# yard-ice-ethernet.net
KiCad netlist of a schematic drawn in Altium Designer
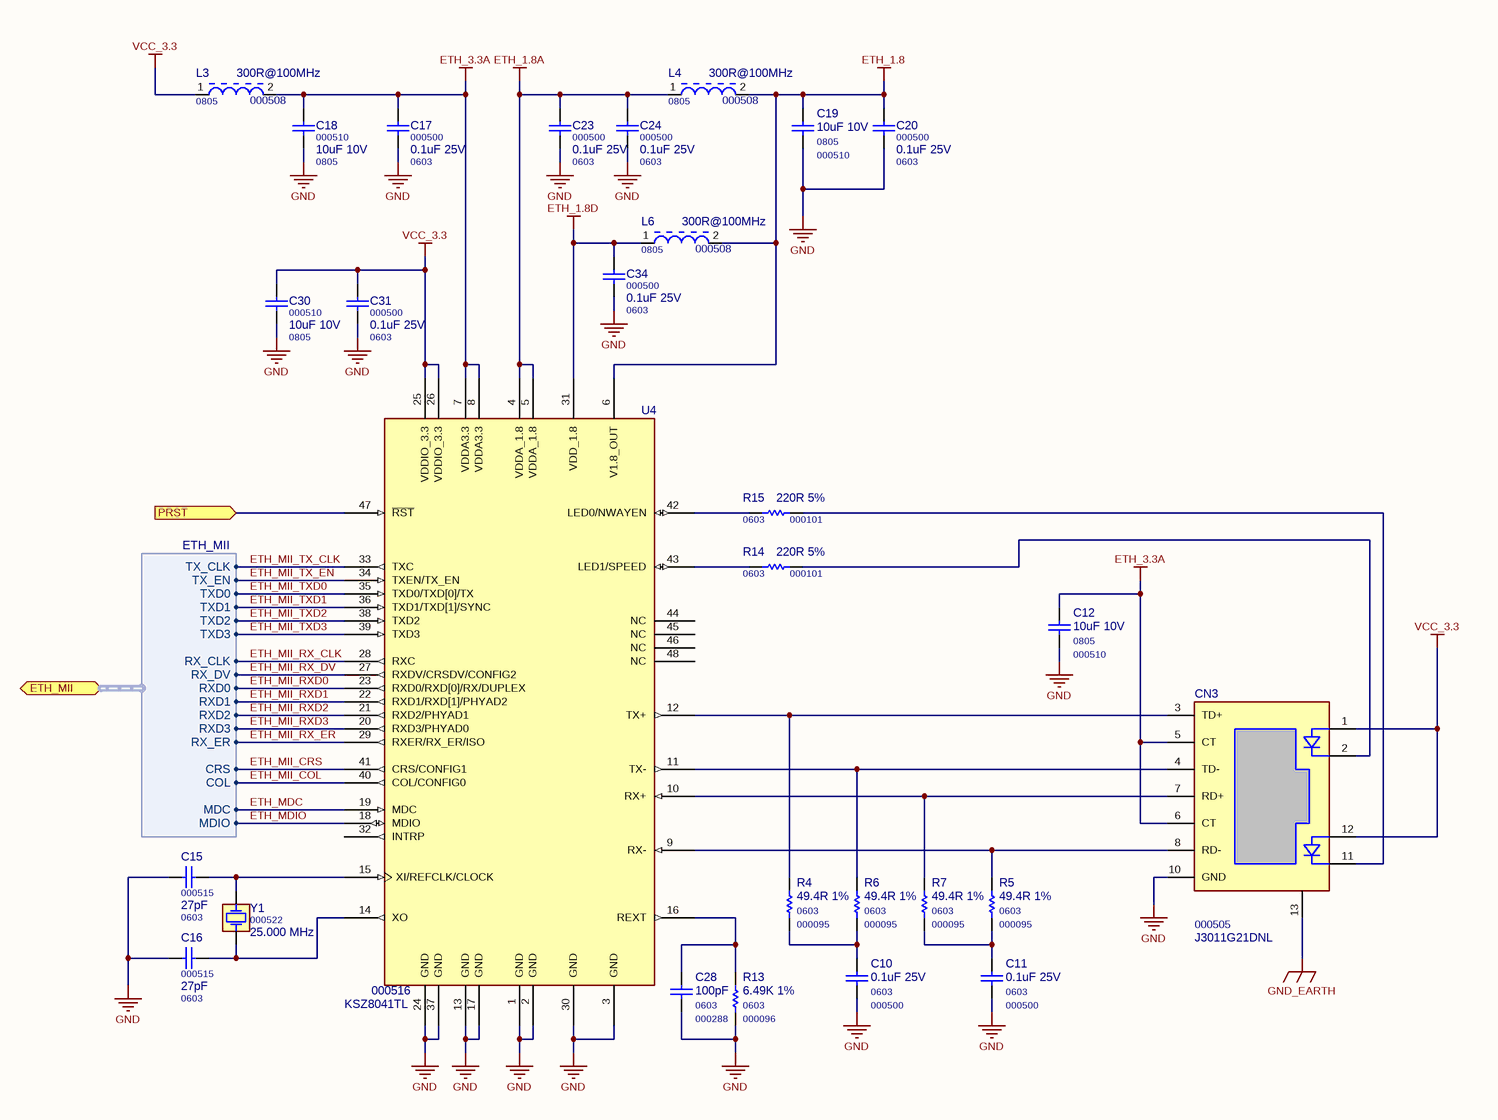
[diagram p0: yard-ice-ethernet.SchDoc]

(export (version "E")
  (design (tool "Eeschema 10.0.6"))
  (components
    (comp (ref "C10")
      (value "000500")
      (footprint "C0603M")
      (description "SMD Ceramic Chip Capacitor - 0603 - X7R")
      (fields
        (field (name "ALTIUM_VALUE") "0.1uF 25V")
        (field (name "PACKAGE") "0603")
        (field (name "MF") "TDK")
      )
      (libsource (lib "discrete-sm") (part "C0603"))
    )
    (comp (ref "C11")
      (value "000500")
      (footprint "C0603M")
      (description "SMD Ceramic Chip Capacitor - 0603 - X7R")
      (fields
        (field (name "ALTIUM_VALUE") "0.1uF 25V")
        (field (name "PACKAGE") "0603")
        (field (name "MF") "TDK")
      )
      (libsource (lib "discrete-sm") (part "C0603"))
    )
    (comp (ref "C12")
      (value "000510")
      (footprint "C0805M")
      (description "SMD Ceramic Chip Capacitor - 0805 - X7R")
      (fields
        (field (name "ALTIUM_VALUE") "10uF 10V")
        (field (name "PACKAGE") "0805")
        (field (name "MF") "TDK")
      )
      (libsource (lib "discrete-sm") (part "C0805"))
    )
    (comp (ref "C15")
      (value "000515")
      (footprint "C0603M")
      (description "SMD Ceramic Chip Capacitor - 0603")
      (fields (field (name "ALTIUM_VALUE") "27pF") (field (name "PACKAGE") "0603"))
      (libsource (lib "discrete-sm") (part "C0603"))
    )
    (comp (ref "C16")
      (value "000515")
      (footprint "C0603M")
      (description "SMD Ceramic Chip Capacitor - 0603")
      (fields (field (name "ALTIUM_VALUE") "27pF") (field (name "PACKAGE") "0603"))
      (libsource (lib "discrete-sm") (part "C0603"))
    )
    (comp (ref "C17")
      (value "000500")
      (footprint "C0603M")
      (description "SMD Ceramic Chip Capacitor - 0603 - X7R")
      (fields
        (field (name "ALTIUM_VALUE") "0.1uF 25V")
        (field (name "PACKAGE") "0603")
        (field (name "MF") "TDK")
      )
      (libsource (lib "discrete-sm") (part "C0603"))
    )
    (comp (ref "C18")
      (value "000510")
      (footprint "C0805M")
      (description "SMD Ceramic Chip Capacitor - 0805 - X7R")
      (fields
        (field (name "ALTIUM_VALUE") "10uF 10V")
        (field (name "PACKAGE") "0805")
        (field (name "MF") "TDK")
      )
      (libsource (lib "discrete-sm") (part "C0805"))
    )
    (comp (ref "C19")
      (value "000510")
      (footprint "C0805M")
      (description "SMD Ceramic Chip Capacitor - 0805 - X7R")
      (fields
        (field (name "ALTIUM_VALUE") "10uF 10V")
        (field (name "PACKAGE") "0805")
        (field (name "MF") "TDK")
      )
      (libsource (lib "discrete-sm") (part "C0805"))
    )
    (comp (ref "C20")
      (value "000500")
      (footprint "C0603M")
      (description "SMD Ceramic Chip Capacitor - 0603 - X7R")
      (fields
        (field (name "ALTIUM_VALUE") "0.1uF 25V")
        (field (name "PACKAGE") "0603")
        (field (name "MF") "TDK")
      )
      (libsource (lib "discrete-sm") (part "C0603"))
    )
    (comp (ref "C23")
      (value "000500")
      (footprint "C0603M")
      (description "SMD Ceramic Chip Capacitor - 0603 - X7R")
      (fields
        (field (name "ALTIUM_VALUE") "0.1uF 25V")
        (field (name "PACKAGE") "0603")
        (field (name "MF") "TDK")
      )
      (libsource (lib "discrete-sm") (part "C0603"))
    )
    (comp (ref "C24")
      (value "000500")
      (footprint "C0603M")
      (description "SMD Ceramic Chip Capacitor - 0603 - X7R")
      (fields
        (field (name "ALTIUM_VALUE") "0.1uF 25V")
        (field (name "PACKAGE") "0603")
        (field (name "MF") "TDK")
      )
      (libsource (lib "discrete-sm") (part "C0603"))
    )
    (comp (ref "C28")
      (value "000288")
      (footprint "C0603M")
      (description "SMD Ceramic Chip Capacitor - 0603")
      (fields (field (name "ALTIUM_VALUE") "100pF") (field (name "PACKAGE") "0603"))
      (libsource (lib "discrete-sm") (part "C0603"))
    )
    (comp (ref "C30")
      (value "000510")
      (footprint "C0805M")
      (description "SMD Ceramic Chip Capacitor - 0805 - X7R")
      (fields
        (field (name "ALTIUM_VALUE") "10uF 10V")
        (field (name "PACKAGE") "0805")
        (field (name "MF") "TDK")
      )
      (libsource (lib "discrete-sm") (part "C0805"))
    )
    (comp (ref "C31")
      (value "000500")
      (footprint "C0603M")
      (description "SMD Ceramic Chip Capacitor - 0603 - X7R")
      (fields
        (field (name "ALTIUM_VALUE") "0.1uF 25V")
        (field (name "PACKAGE") "0603")
        (field (name "MF") "TDK")
      )
      (libsource (lib "discrete-sm") (part "C0603"))
    )
    (comp (ref "C34")
      (value "000500")
      (footprint "C0603M")
      (description "SMD Ceramic Chip Capacitor - 0603 - X7R")
      (fields
        (field (name "ALTIUM_VALUE") "0.1uF 25V")
        (field (name "PACKAGE") "0603")
        (field (name "MF") "TDK")
      )
      (libsource (lib "discrete-sm") (part "C0603"))
    )
    (comp (ref "CN3")
      (value "000505")
      (footprint "MOD-J3")
      (description "10/100Base-TX surface mount RJ45")
      (fields (field (name "ALTIUM_VALUE") "J3011G21DNL") (field (name "MF") "Pulse"))
      (libsource (lib "pulse-mag") (part "J3011G21DNL"))
    )
    (comp (ref "L3")
      (value "000508")
      (footprint "L0805M")
      (description "SMD Ferrite Bead 0805")
      (fields
        (field (name "ALTIUM_VALUE") "300R@100MHz")
        (field (name "PACKAGE") "0805")
        (field (name "MF") "TDK")
      )
      (libsource (lib "discrete-sm") (part "L0805"))
    )
    (comp (ref "L4")
      (value "000508")
      (footprint "L0805M")
      (description "SMD Ferrite Bead 0805")
      (fields
        (field (name "ALTIUM_VALUE") "300R@100MHz")
        (field (name "PACKAGE") "0805")
        (field (name "MF") "TDK")
      )
      (libsource (lib "discrete-sm") (part "L0805"))
    )
    (comp (ref "L6")
      (value "000508")
      (footprint "L0805M")
      (description "SMD Ferrite Bead 0805")
      (fields
        (field (name "ALTIUM_VALUE") "300R@100MHz")
        (field (name "PACKAGE") "0805")
        (field (name "MF") "TDK")
      )
      (libsource (lib "discrete-sm") (part "L0805"))
    )
    (comp (ref "R4")
      (value "000095")
      (footprint "R0603M")
      (description "SMD Chip Resistor - 0603")
      (fields (field (name "ALTIUM_VALUE") "49.4R 1%") (field (name "PACKAGE") "0603"))
      (libsource (lib "discrete-sm") (part "R0603"))
    )
    (comp (ref "R5")
      (value "000095")
      (footprint "R0603M")
      (description "SMD Chip Resistor - 0603")
      (fields (field (name "ALTIUM_VALUE") "49.4R 1%") (field (name "PACKAGE") "0603"))
      (libsource (lib "discrete-sm") (part "R0603"))
    )
    (comp (ref "R6")
      (value "000095")
      (footprint "R0603M")
      (description "SMD Chip Resistor - 0603")
      (fields (field (name "ALTIUM_VALUE") "49.4R 1%") (field (name "PACKAGE") "0603"))
      (libsource (lib "discrete-sm") (part "R0603"))
    )
    (comp (ref "R7")
      (value "000095")
      (footprint "R0603M")
      (description "SMD Chip Resistor - 0603")
      (fields (field (name "ALTIUM_VALUE") "49.4R 1%") (field (name "PACKAGE") "0603"))
      (libsource (lib "discrete-sm") (part "R0603"))
    )
    (comp (ref "R13")
      (value "000096")
      (footprint "R0603M")
      (description "SMD Chip Resistor - 0603")
      (fields (field (name "ALTIUM_VALUE") "6.49K 1%") (field (name "PACKAGE") "0603"))
      (libsource (lib "discrete-sm") (part "R0603"))
    )
    (comp (ref "R14")
      (value "000101")
      (footprint "R0603M")
      (description "SMD Chip Resistor - 0603")
      (fields (field (name "ALTIUM_VALUE") "220R 5%") (field (name "PACKAGE") "0603"))
      (libsource (lib "discrete-sm") (part "R0603"))
    )
    (comp (ref "R15")
      (value "000101")
      (footprint "R0603M")
      (description "SMD Chip Resistor - 0603")
      (fields (field (name "ALTIUM_VALUE") "220R 5%") (field (name "PACKAGE") "0603"))
      (libsource (lib "discrete-sm") (part "R0603"))
    )
    (comp (ref "U4")
      (value "000516")
      (footprint "48-TQFP")
      (description "10Base-T/100Base-TX Physical Layer Transceiver")
      (fields (field (name "ALTIUM_VALUE") "KSZ8041TL") (field (name "MF") "Micrel"))
      (libsource (lib "micrel-ethernet") (part "KSZ8041TL"))
    )
    (comp (ref "Y1")
      (value "000522")
      (footprint "ABM3-H")
      (description "Miniature Ceramic SMD Crystal")
      (fields (field (name "MF") "Abracon") (field (name "ALTIUM_VALUE") "25.000 MHz"))
      (libsource (lib "abracon") (part "ABM3"))
    )
  )
  (nets
    (net (code "2") (name "/ETH_MDC") (class "Default")
      (node (ref "U4") (pin "19") (pinfunction "MDC_19") (pintype "input"))
    )
    (net (code "3") (name "/ETH_MDIO") (class "Default")
      (node (ref "U4") (pin "18") (pinfunction "MDIO_18") (pintype "bidirectional"))
    )
    (net (code "4") (name "/ETH_MII_COL") (class "Default")
      (node (ref "U4") (pin "40") (pinfunction "COL/CONFIG0_40") (pintype "output"))
    )
    (net (code "5") (name "/ETH_MII_CRS") (class "Default")
      (node (ref "U4") (pin "41") (pinfunction "CRS/CONFIG1_41") (pintype "output"))
    )
    (net (code "6") (name "/ETH_MII_RXD0") (class "Default")
      (node (ref "U4") (pin "23") (pinfunction "RXD0/RXD[0]/RX/DUPLEX_23") (pintype "output"))
    )
    (net (code "7") (name "/ETH_MII_RXD1") (class "Default")
      (node (ref "U4") (pin "22") (pinfunction "RXD1/RXD[1]/PHYAD2_22") (pintype "output"))
    )
    (net (code "8") (name "/ETH_MII_RXD2") (class "Default")
      (node (ref "U4") (pin "21") (pinfunction "RXD2/PHYAD1_21") (pintype "output"))
    )
    (net (code "9") (name "/ETH_MII_RXD3") (class "Default")
      (node (ref "U4") (pin "20") (pinfunction "RXD3/PHYAD0_20") (pintype "output"))
    )
    (net (code "10") (name "/ETH_MII_RX_CLK") (class "Default")
      (node (ref "U4") (pin "28") (pinfunction "RXC_28") (pintype "output"))
    )
    (net (code "11") (name "/ETH_MII_RX_DV") (class "Default")
      (node (ref "U4") (pin "27") (pinfunction "RXDV/CRSDV/CONFIG2_27") (pintype "output"))
    )
    (net (code "12") (name "/ETH_MII_RX_ER") (class "Default")
      (node (ref "U4") (pin "29") (pinfunction "RXER/RX_ER/ISO_29") (pintype "output"))
    )
    (net (code "13") (name "/ETH_MII_TXD0") (class "Default")
      (node (ref "U4") (pin "35") (pinfunction "TXD0/TXD[0]/TX_35") (pintype "input"))
    )
    (net (code "14") (name "/ETH_MII_TXD1") (class "Default")
      (node (ref "U4") (pin "36") (pinfunction "TXD1/TXD[1]/SYNC_36") (pintype "input"))
    )
    (net (code "15") (name "/ETH_MII_TXD2") (class "Default")
      (node (ref "U4") (pin "38") (pinfunction "TXD2_38") (pintype "input"))
    )
    (net (code "16") (name "/ETH_MII_TXD3") (class "Default")
      (node (ref "U4") (pin "39") (pinfunction "TXD3_39") (pintype "input"))
    )
    (net (code "17") (name "/ETH_MII_TX_CLK") (class "Default")
      (node (ref "U4") (pin "33") (pinfunction "TXC_33") (pintype "output"))
    )
    (net (code "18") (name "/ETH_MII_TX_EN") (class "Default")
      (node (ref "U4") (pin "34") (pinfunction "TXEN/TX_EN_34") (pintype "input"))
    )
    (net (code "19") (name "/PRST") (class "Default")
      (node (ref "U4") (pin "47") (pinfunction "~{RST}_47") (pintype "input"))
    )
    (net (code "21") (name "ETH_1.8") (class "Default")
      (node (ref "C19") (pin "1") (pinfunction "1_1") (pintype "passive"))
      (node (ref "C20") (pin "1") (pinfunction "1_1") (pintype "passive"))
      (node (ref "L4") (pin "2") (pinfunction "2_2") (pintype "passive"))
      (node (ref "L6") (pin "2") (pinfunction "2_2") (pintype "passive"))
      (node (ref "U4") (pin "6") (pinfunction "V1.8_OUT_6") (pintype "power_in"))
    )
    (net (code "22") (name "ETH_1.8A") (class "Default")
      (node (ref "C23") (pin "1") (pinfunction "1_1") (pintype "passive"))
      (node (ref "C24") (pin "1") (pinfunction "1_1") (pintype "passive"))
      (node (ref "L4") (pin "1") (pinfunction "1_1") (pintype "passive"))
      (node (ref "U4") (pin "4") (pinfunction "VDDA_1.8_4") (pintype "power_in"))
      (node (ref "U4") (pin "5") (pinfunction "VDDA_1.8_5") (pintype "power_in"))
    )
    (net (code "23") (name "ETH_1.8D") (class "Default")
      (node (ref "C34") (pin "1") (pinfunction "1_1") (pintype "passive"))
      (node (ref "L6") (pin "1") (pinfunction "1_1") (pintype "passive"))
      (node (ref "U4") (pin "31") (pinfunction "VDD_1.8_31") (pintype "power_in"))
    )
    (net (code "24") (name "ETH_3.3A") (class "Default")
      (node (ref "C12") (pin "1") (pinfunction "1_1") (pintype "passive"))
      (node (ref "C17") (pin "1") (pinfunction "1_1") (pintype "passive"))
      (node (ref "C18") (pin "1") (pinfunction "1_1") (pintype "passive"))
      (node (ref "CN3") (pin "5") (pinfunction "CT_5") (pintype "passive"))
      (node (ref "CN3") (pin "6") (pinfunction "CT_6") (pintype "passive"))
      (node (ref "L3") (pin "2") (pinfunction "2_2") (pintype "passive"))
      (node (ref "U4") (pin "7") (pinfunction "VDDA3.3_7") (pintype "power_in"))
      (node (ref "U4") (pin "8") (pinfunction "VDDA3.3_8") (pintype "power_in"))
    )
    (net (code "25") (name "GND") (class "Default")
      (node (ref "C10") (pin "2") (pinfunction "2_2") (pintype "passive"))
      (node (ref "C11") (pin "2") (pinfunction "2_2") (pintype "passive"))
      (node (ref "C12") (pin "2") (pinfunction "2_2") (pintype "passive"))
      (node (ref "C15") (pin "1") (pinfunction "1_1") (pintype "passive"))
      (node (ref "C16") (pin "1") (pinfunction "1_1") (pintype "passive"))
      (node (ref "C17") (pin "2") (pinfunction "2_2") (pintype "passive"))
      (node (ref "C18") (pin "2") (pinfunction "2_2") (pintype "passive"))
      (node (ref "C19") (pin "2") (pinfunction "2_2") (pintype "passive"))
      (node (ref "C20") (pin "2") (pinfunction "2_2") (pintype "passive"))
      (node (ref "C23") (pin "2") (pinfunction "2_2") (pintype "passive"))
      (node (ref "C24") (pin "2") (pinfunction "2_2") (pintype "passive"))
      (node (ref "C28") (pin "2") (pinfunction "2_2") (pintype "passive"))
      (node (ref "C30") (pin "2") (pinfunction "2_2") (pintype "passive"))
      (node (ref "C31") (pin "2") (pinfunction "2_2") (pintype "passive"))
      (node (ref "C34") (pin "2") (pinfunction "2_2") (pintype "passive"))
      (node (ref "CN3") (pin "10") (pinfunction "GND_10") (pintype "passive"))
      (node (ref "R13") (pin "1") (pinfunction "1_1") (pintype "passive"))
      (node (ref "U4") (pin "1") (pinfunction "GND_1") (pintype "power_in"))
      (node (ref "U4") (pin "13") (pinfunction "GND_13") (pintype "power_in"))
      (node (ref "U4") (pin "17") (pinfunction "GND_17") (pintype "power_in"))
      (node (ref "U4") (pin "2") (pinfunction "GND_2") (pintype "power_in"))
      (node (ref "U4") (pin "24") (pinfunction "GND_24") (pintype "power_in"))
      (node (ref "U4") (pin "3") (pinfunction "GND_3") (pintype "power_in"))
      (node (ref "U4") (pin "30") (pinfunction "GND_30") (pintype "power_in"))
      (node (ref "U4") (pin "37") (pinfunction "GND_37") (pintype "power_in"))
    )
    (net (code "26") (name "GND_EARTH") (class "Default")
      (node (ref "CN3") (pin "13") (pinfunction "SHIELD_13") (pintype "passive"))
    )
    (net (code "27") (name "Net-(C10-Pad1)") (class "Default")
      (node (ref "C10") (pin "1") (pinfunction "1_1") (pintype "passive"))
      (node (ref "R4") (pin "1") (pinfunction "1_1") (pintype "passive"))
      (node (ref "R6") (pin "1") (pinfunction "1_1") (pintype "passive"))
    )
    (net (code "28") (name "Net-(C11-Pad1)") (class "Default")
      (node (ref "C11") (pin "1") (pinfunction "1_1") (pintype "passive"))
      (node (ref "R5") (pin "1") (pinfunction "1_1") (pintype "passive"))
      (node (ref "R7") (pin "1") (pinfunction "1_1") (pintype "passive"))
    )
    (net (code "29") (name "Net-(CN3-K1)") (class "Default")
      (node (ref "CN3") (pin "11") (pinfunction "K1_11") (pintype "passive"))
      (node (ref "R15") (pin "1") (pinfunction "1_1") (pintype "passive"))
    )
    (net (code "30") (name "Net-(CN3-K2)") (class "Default")
      (node (ref "CN3") (pin "2") (pinfunction "K2_2") (pintype "passive"))
      (node (ref "R14") (pin "1") (pinfunction "1_1") (pintype "passive"))
    )
    (net (code "31") (name "Net-(CN3-RD+)") (class "Default")
      (node (ref "CN3") (pin "7") (pinfunction "RD+_7") (pintype "passive"))
      (node (ref "R7") (pin "2") (pinfunction "2_2") (pintype "passive"))
      (node (ref "U4") (pin "10") (pinfunction "RX+_10") (pintype "input"))
    )
    (net (code "32") (name "Net-(CN3-RD-)") (class "Default")
      (node (ref "CN3") (pin "8") (pinfunction "RD-_8") (pintype "passive"))
      (node (ref "R5") (pin "2") (pinfunction "2_2") (pintype "passive"))
      (node (ref "U4") (pin "9") (pinfunction "RX-_9") (pintype "input"))
    )
    (net (code "33") (name "Net-(CN3-TD+)") (class "Default")
      (node (ref "CN3") (pin "3") (pinfunction "TD+_3") (pintype "passive"))
      (node (ref "R4") (pin "2") (pinfunction "2_2") (pintype "passive"))
      (node (ref "U4") (pin "12") (pinfunction "TX+_12") (pintype "output"))
    )
    (net (code "34") (name "Net-(CN3-TD-)") (class "Default")
      (node (ref "CN3") (pin "4") (pinfunction "TD-_4") (pintype "passive"))
      (node (ref "R6") (pin "2") (pinfunction "2_2") (pintype "passive"))
      (node (ref "U4") (pin "11") (pinfunction "TX-_11") (pintype "output"))
    )
    (net (code "35") (name "Net-(U4-LED0{slash}NWAYEN)") (class "Default")
      (node (ref "R15") (pin "2") (pinfunction "2_2") (pintype "passive"))
      (node (ref "U4") (pin "42") (pinfunction "LED0/NWAYEN_42") (pintype "bidirectional"))
    )
    (net (code "36") (name "Net-(U4-LED1{slash}SPEED)") (class "Default")
      (node (ref "R14") (pin "2") (pinfunction "2_2") (pintype "passive"))
      (node (ref "U4") (pin "43") (pinfunction "LED1/SPEED_43") (pintype "bidirectional"))
    )
    (net (code "37") (name "Net-(U4-REXT)") (class "Default")
      (node (ref "C28") (pin "1") (pinfunction "1_1") (pintype "passive"))
      (node (ref "R13") (pin "2") (pinfunction "2_2") (pintype "passive"))
      (node (ref "U4") (pin "16") (pinfunction "REXT_16") (pintype "output"))
    )
    (net (code "38") (name "Net-(U4-XI{slash}REFCLK{slash}CLOCK)") (class "Default")
      (node (ref "C15") (pin "2") (pinfunction "2_2") (pintype "passive"))
      (node (ref "U4") (pin "15") (pinfunction "XI/REFCLK/CLOCK_15") (pintype "input"))
      (node (ref "Y1") (pin "1") (pinfunction "1_1") (pintype "passive"))
    )
    (net (code "39") (name "Net-(U4-XO)") (class "Default")
      (node (ref "C16") (pin "2") (pinfunction "2_2") (pintype "passive"))
      (node (ref "U4") (pin "14") (pinfunction "XO_14") (pintype "output"))
      (node (ref "Y1") (pin "2") (pinfunction "2_2") (pintype "passive"))
    )
    (net (code "40") (name "VCC_3.3") (class "Default")
      (node (ref "C30") (pin "1") (pinfunction "1_1") (pintype "passive"))
      (node (ref "C31") (pin "1") (pinfunction "1_1") (pintype "passive"))
      (node (ref "CN3") (pin "1") (pinfunction "A2_1") (pintype "passive"))
      (node (ref "CN3") (pin "12") (pinfunction "A1_12") (pintype "passive"))
      (node (ref "L3") (pin "1") (pinfunction "1_1") (pintype "passive"))
      (node (ref "U4") (pin "25") (pinfunction "VDDIO_3.3_25") (pintype "power_in"))
      (node (ref "U4") (pin "26") (pinfunction "VDDIO_3.3_26") (pintype "power_in"))
    )
    (net (code "41") (name "unconnected-(U4-INTRP-Pad32)") (class "Default")
      (node (ref "U4") (pin "32") (pinfunction "INTRP_32") (pintype "output"))
    )
    (net (code "42") (name "unconnected-(U4-NC-Pad44)") (class "Default")
      (node (ref "U4") (pin "44") (pinfunction "NC_44") (pintype "passive"))
    )
    (net (code "43") (name "unconnected-(U4-NC-Pad45)") (class "Default")
      (node (ref "U4") (pin "45") (pinfunction "NC_45") (pintype "passive"))
    )
    (net (code "44") (name "unconnected-(U4-NC-Pad46)") (class "Default")
      (node (ref "U4") (pin "46") (pinfunction "NC_46") (pintype "passive"))
    )
    (net (code "45") (name "unconnected-(U4-NC-Pad48)") (class "Default")
      (node (ref "U4") (pin "48") (pinfunction "NC_48") (pintype "passive"))
    )
  )
)
